# IRsensor_Relayx4_Controller.net
KiCad netlist of a schematic drawn in Altium Designer
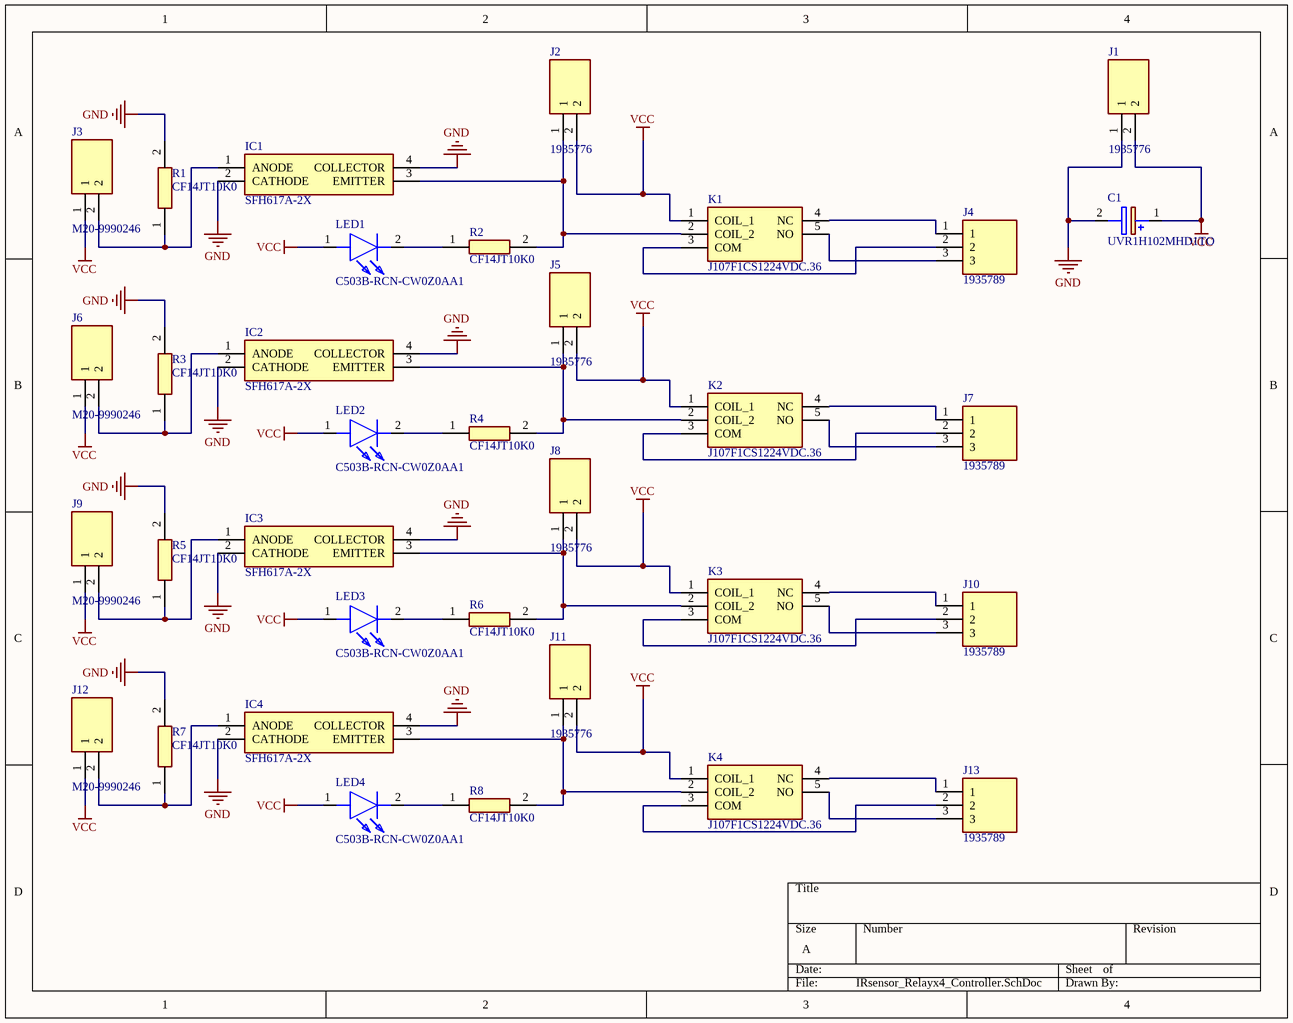
[diagram p0: IRsensor_Relayx4_Controller.SchDoc]

(export (version "E")
  (design (tool "Eeschema 10.0.6"))
  (components
    (comp (ref "C1")
      (value "UVR1H102MHD1TO")
      (footprint "SamacSys:CAPPRD500W60D1275H2700")
      (description "Capacitor Polarised")
      (fields (field (name "MOUSER PART NUMBER") "647-UVR1H102MHD1T0"))
      (libsource (lib "SamacSys") (part "UVR1H102MHD1TO"))
    )
    (comp (ref "IC1")
      (value "SFH617A-2X")
      (footprint "SamacSys:DIP762W50P254L458H400Q4N")
      (description "Integrated Circuit")
      (libsource (lib "SamacSys") (part "SFH617A-2X"))
    )
    (comp (ref "IC2")
      (value "SFH617A-2X")
      (footprint "SamacSys:DIP762W50P254L458H400Q4N")
      (description "Integrated Circuit")
      (libsource (lib "SamacSys") (part "SFH617A-2X"))
    )
    (comp (ref "IC3")
      (value "SFH617A-2X")
      (footprint "SamacSys:DIP762W50P254L458H400Q4N")
      (description "Integrated Circuit")
      (libsource (lib "SamacSys") (part "SFH617A-2X"))
    )
    (comp (ref "IC4")
      (value "SFH617A-2X")
      (footprint "SamacSys:DIP762W50P254L458H400Q4N")
      (description "Integrated Circuit")
      (libsource (lib "SamacSys") (part "SFH617A-2X"))
    )
    (comp (ref "J1")
      (value "1935776")
      (footprint "SamacSys:1935776")
      (description "Connector")
      (fields (field (name "MOUSER PART NUMBER") "651-1935776"))
      (libsource (lib "SamacSys") (part "1935776"))
    )
    (comp (ref "J2")
      (value "1935776")
      (footprint "SamacSys:1935776")
      (description "Connector")
      (fields (field (name "MOUSER PART NUMBER") "651-1935776"))
      (libsource (lib "SamacSys") (part "1935776"))
    )
    (comp (ref "J3")
      (value "M20-9990246")
      (footprint "SamacSys:HDRV2W66P0X254_1X2_508X254X874P")
      (description "Connector")
      (fields (field (name "MOUSER PART NUMBER") "855-M20-9990246"))
      (libsource (lib "SamacSys") (part "M20-9990246"))
    )
    (comp (ref "J4")
      (value "1935789")
      (footprint "SamacSys:1935789")
      (description "Connector")
      (fields (field (name "MOUSER PART NUMBER") "651-1935789"))
      (libsource (lib "SamacSys") (part "1935789"))
    )
    (comp (ref "J5")
      (value "1935776")
      (footprint "SamacSys:1935776")
      (description "Connector")
      (fields (field (name "MOUSER PART NUMBER") "651-1935776"))
      (libsource (lib "SamacSys") (part "1935776"))
    )
    (comp (ref "J6")
      (value "M20-9990246")
      (footprint "SamacSys:HDRV2W66P0X254_1X2_508X254X874P")
      (description "Connector")
      (fields (field (name "MOUSER PART NUMBER") "855-M20-9990246"))
      (libsource (lib "SamacSys") (part "M20-9990246"))
    )
    (comp (ref "J7")
      (value "1935789")
      (footprint "SamacSys:1935789")
      (description "Connector")
      (fields (field (name "MOUSER PART NUMBER") "651-1935789"))
      (libsource (lib "SamacSys") (part "1935789"))
    )
    (comp (ref "J8")
      (value "1935776")
      (footprint "SamacSys:1935776")
      (description "Connector")
      (fields (field (name "MOUSER PART NUMBER") "651-1935776"))
      (libsource (lib "SamacSys") (part "1935776"))
    )
    (comp (ref "J9")
      (value "M20-9990246")
      (footprint "SamacSys:HDRV2W66P0X254_1X2_508X254X874P")
      (description "Connector")
      (fields (field (name "MOUSER PART NUMBER") "855-M20-9990246"))
      (libsource (lib "SamacSys") (part "M20-9990246"))
    )
    (comp (ref "J10")
      (value "1935789")
      (footprint "SamacSys:1935789")
      (description "Connector")
      (fields (field (name "MOUSER PART NUMBER") "651-1935789"))
      (libsource (lib "SamacSys") (part "1935789"))
    )
    (comp (ref "J11")
      (value "1935776")
      (footprint "SamacSys:1935776")
      (description "Connector")
      (fields (field (name "MOUSER PART NUMBER") "651-1935776"))
      (libsource (lib "SamacSys") (part "1935776"))
    )
    (comp (ref "J12")
      (value "M20-9990246")
      (footprint "SamacSys:HDRV2W66P0X254_1X2_508X254X874P")
      (description "Connector")
      (fields (field (name "MOUSER PART NUMBER") "855-M20-9990246"))
      (libsource (lib "SamacSys") (part "M20-9990246"))
    )
    (comp (ref "J13")
      (value "1935789")
      (footprint "SamacSys:1935789")
      (description "Connector")
      (fields (field (name "MOUSER PART NUMBER") "651-1935789"))
      (libsource (lib "SamacSys") (part "1935789"))
    )
    (comp (ref "K1")
      (value "J107F1CS1224VDC.36")
      (footprint "SamacSys:J107F1CS1224VDC36")
      (description "Relay or Contactor")
      (libsource (lib "SamacSys") (part "J107F1CS1224VDC.36"))
    )
    (comp (ref "K2")
      (value "J107F1CS1224VDC.36")
      (footprint "SamacSys:J107F1CS1224VDC36")
      (description "Relay or Contactor")
      (libsource (lib "SamacSys") (part "J107F1CS1224VDC.36"))
    )
    (comp (ref "K3")
      (value "J107F1CS1224VDC.36")
      (footprint "SamacSys:J107F1CS1224VDC36")
      (description "Relay or Contactor")
      (libsource (lib "SamacSys") (part "J107F1CS1224VDC.36"))
    )
    (comp (ref "K4")
      (value "J107F1CS1224VDC.36")
      (footprint "SamacSys:J107F1CS1224VDC36")
      (description "Relay or Contactor")
      (libsource (lib "SamacSys") (part "J107F1CS1224VDC.36"))
    )
    (comp (ref "LED1")
      (value "C503B-RCN-CW0Z0AA1")
      (footprint "SamacSys:C503BRCNCW0Z0AA1")
      (description "LED")
      (fields (field (name "MOUSER PART NUMBER") "941-C503BRCNCW0Z0AA1"))
      (libsource (lib "SamacSys") (part "C503B-RCN-CW0Z0AA1"))
    )
    (comp (ref "LED2")
      (value "C503B-RCN-CW0Z0AA1")
      (footprint "SamacSys:C503BRCNCW0Z0AA1")
      (description "LED")
      (fields (field (name "MOUSER PART NUMBER") "941-C503BRCNCW0Z0AA1"))
      (libsource (lib "SamacSys") (part "C503B-RCN-CW0Z0AA1"))
    )
    (comp (ref "LED3")
      (value "C503B-RCN-CW0Z0AA1")
      (footprint "SamacSys:C503BRCNCW0Z0AA1")
      (description "LED")
      (fields (field (name "MOUSER PART NUMBER") "941-C503BRCNCW0Z0AA1"))
      (libsource (lib "SamacSys") (part "C503B-RCN-CW0Z0AA1"))
    )
    (comp (ref "LED4")
      (value "C503B-RCN-CW0Z0AA1")
      (footprint "SamacSys:C503BRCNCW0Z0AA1")
      (description "LED")
      (fields (field (name "MOUSER PART NUMBER") "941-C503BRCNCW0Z0AA1"))
      (libsource (lib "SamacSys") (part "C503B-RCN-CW0Z0AA1"))
    )
    (comp (ref "R1")
      (value "CF14JT10K0")
      (footprint "SamacSys:RESAD1520W63L600D230")
      (description "Resistor")
      (libsource (lib "SamacSys") (part "CF14JT10K0"))
    )
    (comp (ref "R2")
      (value "CF14JT10K0")
      (footprint "SamacSys:RESAD1520W63L600D230")
      (description "Resistor")
      (libsource (lib "") (part "CF14JT10K0_1"))
    )
    (comp (ref "R3")
      (value "CF14JT10K0")
      (footprint "SamacSys:RESAD1520W63L600D230")
      (description "Resistor")
      (libsource (lib "SamacSys") (part "CF14JT10K0"))
    )
    (comp (ref "R4")
      (value "CF14JT10K0")
      (footprint "SamacSys:RESAD1520W63L600D230")
      (description "Resistor")
      (libsource (lib "") (part "CF14JT10K0_1"))
    )
    (comp (ref "R5")
      (value "CF14JT10K0")
      (footprint "SamacSys:RESAD1520W63L600D230")
      (description "Resistor")
      (libsource (lib "SamacSys") (part "CF14JT10K0"))
    )
    (comp (ref "R6")
      (value "CF14JT10K0")
      (footprint "SamacSys:RESAD1520W63L600D230")
      (description "Resistor")
      (libsource (lib "") (part "CF14JT10K0_1"))
    )
    (comp (ref "R7")
      (value "CF14JT10K0")
      (footprint "SamacSys:RESAD1520W63L600D230")
      (description "Resistor")
      (libsource (lib "SamacSys") (part "CF14JT10K0"))
    )
    (comp (ref "R8")
      (value "CF14JT10K0")
      (footprint "SamacSys:RESAD1520W63L600D230")
      (description "Resistor")
      (libsource (lib "") (part "CF14JT10K0_1"))
    )
  )
  (nets
    (net (code "1") (name "GND") (class "Default")
      (node (ref "C1") (pin "2") (pinfunction "-_2") (pintype "passive"))
      (node (ref "IC1") (pin "2") (pinfunction "CATHODE_2") (pintype "passive"))
      (node (ref "IC1") (pin "4") (pinfunction "COLLECTOR_4") (pintype "passive"))
      (node (ref "IC2") (pin "2") (pinfunction "CATHODE_2") (pintype "passive"))
      (node (ref "IC2") (pin "4") (pinfunction "COLLECTOR_4") (pintype "passive"))
      (node (ref "IC3") (pin "2") (pinfunction "CATHODE_2") (pintype "passive"))
      (node (ref "IC3") (pin "4") (pinfunction "COLLECTOR_4") (pintype "passive"))
      (node (ref "IC4") (pin "2") (pinfunction "CATHODE_2") (pintype "passive"))
      (node (ref "IC4") (pin "4") (pinfunction "COLLECTOR_4") (pintype "passive"))
      (node (ref "J1") (pin "1") (pinfunction "1_1") (pintype "passive"))
      (node (ref "R1") (pin "2") (pinfunction "2_2") (pintype "passive"))
      (node (ref "R3") (pin "2") (pinfunction "2_2") (pintype "passive"))
      (node (ref "R5") (pin "2") (pinfunction "2_2") (pintype "passive"))
      (node (ref "R7") (pin "2") (pinfunction "2_2") (pintype "passive"))
    )
    (net (code "2") (name "Net-(IC1-ANODE)") (class "Default")
      (node (ref "IC1") (pin "1") (pinfunction "ANODE_1") (pintype "passive"))
      (node (ref "J3") (pin "2") (pinfunction "2_2") (pintype "passive"))
      (node (ref "R1") (pin "1") (pinfunction "1_1") (pintype "passive"))
    )
    (net (code "3") (name "Net-(IC1-EMITTER)") (class "Default")
      (node (ref "IC1") (pin "3") (pinfunction "EMITTER_3") (pintype "passive"))
      (node (ref "J2") (pin "1") (pinfunction "1_1") (pintype "passive"))
      (node (ref "K1") (pin "2") (pinfunction "COIL_2_2") (pintype "passive"))
      (node (ref "R2") (pin "2") (pinfunction "2_2") (pintype "passive"))
    )
    (net (code "4") (name "Net-(IC2-ANODE)") (class "Default")
      (node (ref "IC2") (pin "1") (pinfunction "ANODE_1") (pintype "passive"))
      (node (ref "J6") (pin "2") (pinfunction "2_2") (pintype "passive"))
      (node (ref "R3") (pin "1") (pinfunction "1_1") (pintype "passive"))
    )
    (net (code "5") (name "Net-(IC2-EMITTER)") (class "Default")
      (node (ref "IC2") (pin "3") (pinfunction "EMITTER_3") (pintype "passive"))
      (node (ref "J5") (pin "1") (pinfunction "1_1") (pintype "passive"))
      (node (ref "K2") (pin "2") (pinfunction "COIL_2_2") (pintype "passive"))
      (node (ref "R4") (pin "2") (pinfunction "2_2") (pintype "passive"))
    )
    (net (code "6") (name "Net-(IC3-ANODE)") (class "Default")
      (node (ref "IC3") (pin "1") (pinfunction "ANODE_1") (pintype "passive"))
      (node (ref "J9") (pin "2") (pinfunction "2_2") (pintype "passive"))
      (node (ref "R5") (pin "1") (pinfunction "1_1") (pintype "passive"))
    )
    (net (code "7") (name "Net-(IC3-EMITTER)") (class "Default")
      (node (ref "IC3") (pin "3") (pinfunction "EMITTER_3") (pintype "passive"))
      (node (ref "J8") (pin "1") (pinfunction "1_1") (pintype "passive"))
      (node (ref "K3") (pin "2") (pinfunction "COIL_2_2") (pintype "passive"))
      (node (ref "R6") (pin "2") (pinfunction "2_2") (pintype "passive"))
    )
    (net (code "8") (name "Net-(IC4-ANODE)") (class "Default")
      (node (ref "IC4") (pin "1") (pinfunction "ANODE_1") (pintype "passive"))
      (node (ref "J12") (pin "2") (pinfunction "2_2") (pintype "passive"))
      (node (ref "R7") (pin "1") (pinfunction "1_1") (pintype "passive"))
    )
    (net (code "9") (name "Net-(IC4-EMITTER)") (class "Default")
      (node (ref "IC4") (pin "3") (pinfunction "EMITTER_3") (pintype "passive"))
      (node (ref "J11") (pin "1") (pinfunction "1_1") (pintype "passive"))
      (node (ref "K4") (pin "2") (pinfunction "COIL_2_2") (pintype "passive"))
      (node (ref "R8") (pin "2") (pinfunction "2_2") (pintype "passive"))
    )
    (net (code "10") (name "Net-(K1-COM)") (class "Default")
      (node (ref "J4") (pin "2") (pinfunction "2_2") (pintype "passive"))
      (node (ref "K1") (pin "3") (pinfunction "COM_3") (pintype "passive"))
    )
    (net (code "11") (name "Net-(K1-NC)") (class "Default")
      (node (ref "J4") (pin "1") (pinfunction "1_1") (pintype "passive"))
      (node (ref "K1") (pin "4") (pinfunction "NC_4") (pintype "passive"))
    )
    (net (code "12") (name "Net-(K1-NO)") (class "Default")
      (node (ref "J4") (pin "3") (pinfunction "3_3") (pintype "passive"))
      (node (ref "K1") (pin "5") (pinfunction "NO_5") (pintype "passive"))
    )
    (net (code "13") (name "Net-(K2-COM)") (class "Default")
      (node (ref "J7") (pin "2") (pinfunction "2_2") (pintype "passive"))
      (node (ref "K2") (pin "3") (pinfunction "COM_3") (pintype "passive"))
    )
    (net (code "14") (name "Net-(K2-NC)") (class "Default")
      (node (ref "J7") (pin "1") (pinfunction "1_1") (pintype "passive"))
      (node (ref "K2") (pin "4") (pinfunction "NC_4") (pintype "passive"))
    )
    (net (code "15") (name "Net-(K2-NO)") (class "Default")
      (node (ref "J7") (pin "3") (pinfunction "3_3") (pintype "passive"))
      (node (ref "K2") (pin "5") (pinfunction "NO_5") (pintype "passive"))
    )
    (net (code "16") (name "Net-(K3-COM)") (class "Default")
      (node (ref "J10") (pin "2") (pinfunction "2_2") (pintype "passive"))
      (node (ref "K3") (pin "3") (pinfunction "COM_3") (pintype "passive"))
    )
    (net (code "17") (name "Net-(K3-NC)") (class "Default")
      (node (ref "J10") (pin "1") (pinfunction "1_1") (pintype "passive"))
      (node (ref "K3") (pin "4") (pinfunction "NC_4") (pintype "passive"))
    )
    (net (code "18") (name "Net-(K3-NO)") (class "Default")
      (node (ref "J10") (pin "3") (pinfunction "3_3") (pintype "passive"))
      (node (ref "K3") (pin "5") (pinfunction "NO_5") (pintype "passive"))
    )
    (net (code "19") (name "Net-(K4-COM)") (class "Default")
      (node (ref "J13") (pin "2") (pinfunction "2_2") (pintype "passive"))
      (node (ref "K4") (pin "3") (pinfunction "COM_3") (pintype "passive"))
    )
    (net (code "20") (name "Net-(K4-NC)") (class "Default")
      (node (ref "J13") (pin "1") (pinfunction "1_1") (pintype "passive"))
      (node (ref "K4") (pin "4") (pinfunction "NC_4") (pintype "passive"))
    )
    (net (code "21") (name "Net-(K4-NO)") (class "Default")
      (node (ref "J13") (pin "3") (pinfunction "3_3") (pintype "passive"))
      (node (ref "K4") (pin "5") (pinfunction "NO_5") (pintype "passive"))
    )
    (net (code "22") (name "Net-(LED1-K)") (class "Default")
      (node (ref "LED1") (pin "2") (pinfunction "K_2") (pintype "passive"))
      (node (ref "R2") (pin "1") (pinfunction "1_1") (pintype "passive"))
    )
    (net (code "23") (name "Net-(LED2-K)") (class "Default")
      (node (ref "LED2") (pin "2") (pinfunction "K_2") (pintype "passive"))
      (node (ref "R4") (pin "1") (pinfunction "1_1") (pintype "passive"))
    )
    (net (code "24") (name "Net-(LED3-K)") (class "Default")
      (node (ref "LED3") (pin "2") (pinfunction "K_2") (pintype "passive"))
      (node (ref "R6") (pin "1") (pinfunction "1_1") (pintype "passive"))
    )
    (net (code "25") (name "Net-(LED4-K)") (class "Default")
      (node (ref "LED4") (pin "2") (pinfunction "K_2") (pintype "passive"))
      (node (ref "R8") (pin "1") (pinfunction "1_1") (pintype "passive"))
    )
    (net (code "26") (name "VCC") (class "Default")
      (node (ref "C1") (pin "1") (pinfunction "+_1") (pintype "passive"))
      (node (ref "J1") (pin "2") (pinfunction "2_2") (pintype "passive"))
      (node (ref "J11") (pin "2") (pinfunction "2_2") (pintype "passive"))
      (node (ref "J12") (pin "1") (pinfunction "1_1") (pintype "passive"))
      (node (ref "J2") (pin "2") (pinfunction "2_2") (pintype "passive"))
      (node (ref "J3") (pin "1") (pinfunction "1_1") (pintype "passive"))
      (node (ref "J5") (pin "2") (pinfunction "2_2") (pintype "passive"))
      (node (ref "J6") (pin "1") (pinfunction "1_1") (pintype "passive"))
      (node (ref "J8") (pin "2") (pinfunction "2_2") (pintype "passive"))
      (node (ref "J9") (pin "1") (pinfunction "1_1") (pintype "passive"))
      (node (ref "K1") (pin "1") (pinfunction "COIL_1_1") (pintype "passive"))
      (node (ref "K2") (pin "1") (pinfunction "COIL_1_1") (pintype "passive"))
      (node (ref "K3") (pin "1") (pinfunction "COIL_1_1") (pintype "passive"))
      (node (ref "K4") (pin "1") (pinfunction "COIL_1_1") (pintype "passive"))
      (node (ref "LED1") (pin "1") (pinfunction "A_1") (pintype "passive"))
      (node (ref "LED2") (pin "1") (pinfunction "A_1") (pintype "passive"))
      (node (ref "LED3") (pin "1") (pinfunction "A_1") (pintype "passive"))
      (node (ref "LED4") (pin "1") (pinfunction "A_1") (pintype "passive"))
    )
  )
)
